# BACKPMAN21_Intfs.net
KiCad netlist of a schematic drawn in Altium Designer
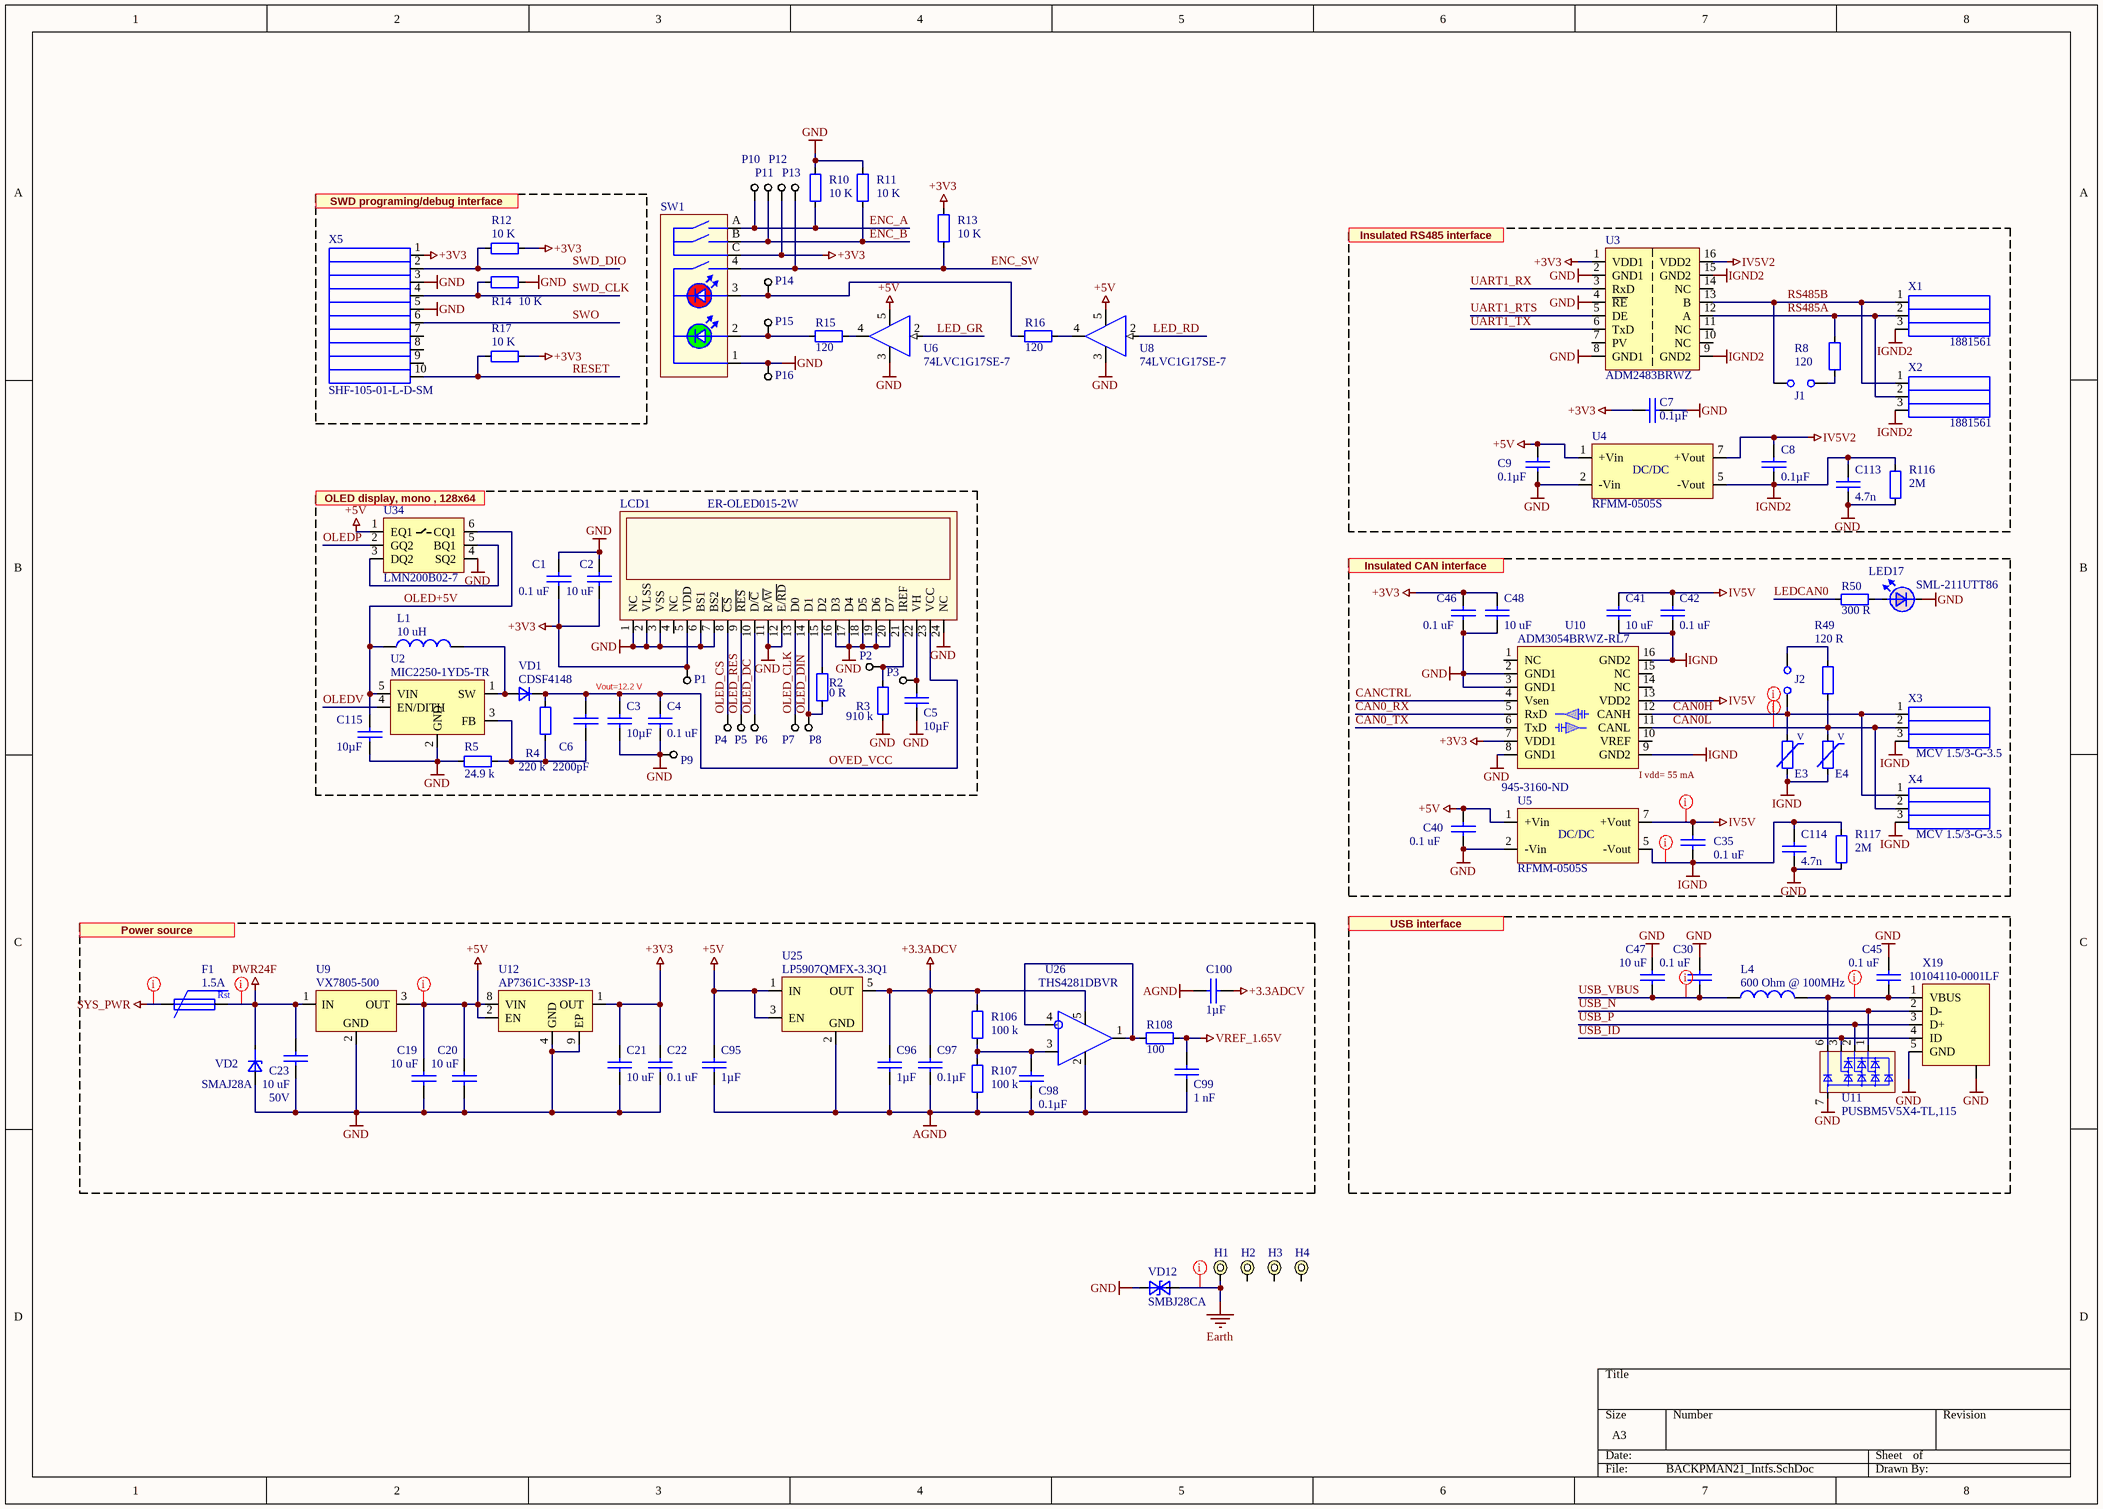
[diagram p0: BACKPMAN21_Intfs.SchDoc]

(export (version "E")
  (design (tool "Eeschema 10.0.6"))
  (components
    (comp (ref "C1")
      (value "0.1 uF")
      (footprint "1608[0603]")
      (description "0.1 uF, 50V, 10% , X7R,  0603 SMD MLC Capacitor")
      (fields (field (name "TOLERANCE") "±10%") (field (name "MANUFACTURER") "WALSIN"))
      (libsource (lib "ea_Capacitors") (part "CVNF100K0603-25"))
    )
    (comp (ref "C2")
      (value "10 uF")
      (footprint "0805-1206")
      (description "CAP CER 10UF 10V 10% X5R 0805")
      (fields (field (name "MANUFACTURER") "Taiyo Yuden") (field (name "TOLERANCE") "10%"))
      (libsource (lib "ea_Capacitors") (part "LMK212F106ZG-T"))
    )
    (comp (ref "C3")
      (value "10µF")
      (footprint "0805 CAP")
      (description "10µF, ±10%, 25V, X5R, 0805 (2012 Metric), -55°C ~ 85°C, -, General Purpose")
      (fields (field (name "PART NUMBER") "TMK212BBJ106KG-T") (field (name "MANUFACTURER") "Taiyo Yuden"))
      (libsource (lib "ea_PassivComps") (part "Capacitor"))
    )
    (comp (ref "C4")
      (value "0.1 uF")
      (footprint "1608[0603]")
      (description "0.1 uF, 50V, 10% , X7R,  0603 SMD MLC Capacitor")
      (fields (field (name "TOLERANCE") "±10%") (field (name "MANUFACTURER") "WALSIN"))
      (libsource (lib "ea_Capacitors") (part "CVNF100K0603-25"))
    )
    (comp (ref "C5")
      (value "10µF")
      (footprint "0805 CAP")
      (description "10µF, ±10%, 25V, X5R, 0805 (2012 Metric), -55°C ~ 85°C, -, General Purpose")
      (fields (field (name "PART NUMBER") "TMK212BBJ106KG-T") (field (name "MANUFACTURER") "Taiyo Yuden"))
      (libsource (lib "ea_PassivComps") (part "Capacitor"))
    )
    (comp (ref "C6")
      (value "2200pF")
      (footprint "0603 CAP")
      (description "2200pF, ±10%, 25V, X7R, 0603 (1608 Metric), -55°C ~ 125°C, -, General Purpose")
      (fields (field (name "PART NUMBER") "CC0603KRX7R8BB222") (field (name "MANUFACTURER") "Yageo"))
      (libsource (lib "ea_PassivComps") (part "Capacitor"))
    )
    (comp (ref "C7")
      (value "0.1µF")
      (footprint "0603 CAP")
      (description "0.1µF, ±10%, 16V, X7R, 0603 (1608 Metric), -55°C ~ 125°C, -, General Purpose")
      (fields
        (field (name "PART NUMBER") "CL10B104KO8NNNC")
        (field (name "MANUFACTURER") "Samsung Electro-Mechanics")
      )
      (libsource (lib "ea_PassivComps") (part "Capacitor"))
    )
    (comp (ref "C8")
      (value "0.1µF")
      (footprint "0603 CAP")
      (description "0.1µF, ±10%, 16V, X7R, 0603 (1608 Metric), -55°C ~ 125°C, -, General Purpose")
      (fields
        (field (name "PART NUMBER") "CL10B104KO8NNNC")
        (field (name "MANUFACTURER") "Samsung Electro-Mechanics")
      )
      (libsource (lib "ea_PassivComps") (part "Capacitor"))
    )
    (comp (ref "C9")
      (value "0.1µF")
      (footprint "0603 CAP")
      (description "0.1µF, ±10%, 16V, X7R, 0603 (1608 Metric), -55°C ~ 125°C, -, General Purpose")
      (fields
        (field (name "PART NUMBER") "CL10B104KO8NNNC")
        (field (name "MANUFACTURER") "Samsung Electro-Mechanics")
      )
      (libsource (lib "ea_PassivComps") (part "Capacitor"))
    )
    (comp (ref "C19")
      (value "10 uF")
      (footprint "0805-1206")
      (description "CAP CER 10UF 10V 10% X5R 0805")
      (fields (field (name "MANUFACTURER") "Taiyo Yuden") (field (name "TOLERANCE") "10%"))
      (libsource (lib "ea_Capacitors") (part "LMK212F106ZG-T"))
    )
    (comp (ref "C20")
      (value "10 uF")
      (footprint "0805-1206")
      (description "CAP CER 10UF 10V 10% X5R 0805")
      (fields (field (name "MANUFACTURER") "Taiyo Yuden") (field (name "TOLERANCE") "10%"))
      (libsource (lib "ea_Capacitors") (part "LMK212F106ZG-T"))
    )
    (comp (ref "C21")
      (value "10 uF")
      (footprint "0805-1206")
      (description "CAP CER 10UF 10V 10% X5R 0805")
      (fields (field (name "MANUFACTURER") "Taiyo Yuden") (field (name "TOLERANCE") "10%"))
      (libsource (lib "ea_Capacitors") (part "LMK212F106ZG-T"))
    )
    (comp (ref "C22")
      (value "0.1 uF")
      (footprint "1608[0603]")
      (description "0.1 uF, 50V, 10% , X7R,  0603 SMD MLC Capacitor")
      (fields (field (name "TOLERANCE") "±10%") (field (name "MANUFACTURER") "WALSIN"))
      (libsource (lib "ea_Capacitors") (part "CVNF100K0603-25"))
    )
    (comp (ref "C23")
      (value "10 uF")
      (footprint "3225[1210]")
      (description "10uF, 50V, 20%, Y5V (F), 1210")
      (fields
        (field (name "MANUFACTURER") "Taiyo Yuden")
        (field (name "TOLERANCE") "20%")
        (field (name "VOLTAGE") "50V")
      )
      (libsource (lib "ea_Capacitors") (part "GRM32DF51H106ZA01L"))
    )
    (comp (ref "C30")
      (value "0.1 uF")
      (footprint "1608[0603]")
      (description "0.1 uF, 50V, 10% , X7R,  0603 SMD MLC Capacitor")
      (fields (field (name "TOLERANCE") "±10%") (field (name "MANUFACTURER") "WALSIN"))
      (libsource (lib "ea_Capacitors") (part "CVNF100K0603-25"))
    )
    (comp (ref "C35")
      (value "0.1 uF")
      (footprint "1608[0603]")
      (description "0.1 uF, 50V, 10% , X7R,  0603 SMD MLC Capacitor")
      (fields (field (name "TOLERANCE") "±10%") (field (name "MANUFACTURER") "WALSIN"))
      (libsource (lib "ea_Capacitors") (part "CVNF100K0603-25"))
    )
    (comp (ref "C40")
      (value "0.1 uF")
      (footprint "1608[0603]")
      (description "0.1 uF, 50V, 10% , X7R,  0603 SMD MLC Capacitor")
      (fields (field (name "TOLERANCE") "±10%") (field (name "MANUFACTURER") "WALSIN"))
      (libsource (lib "ea_Capacitors") (part "CVNF100K0603-25"))
    )
    (comp (ref "C41")
      (value "10 uF")
      (footprint "0805-1206")
      (description "CAP CER 10UF 10V 10% X5R 0805")
      (fields (field (name "MANUFACTURER") "Taiyo Yuden") (field (name "TOLERANCE") "10%"))
      (libsource (lib "ea_Capacitors") (part "LMK212F106ZG-T"))
    )
    (comp (ref "C42")
      (value "0.1 uF")
      (footprint "1608[0603]")
      (description "0.1 uF, 50V, 10% , X7R,  0603 SMD MLC Capacitor")
      (fields (field (name "TOLERANCE") "±10%") (field (name "MANUFACTURER") "WALSIN"))
      (libsource (lib "ea_Capacitors") (part "CVNF100K0603-25"))
    )
    (comp (ref "C45")
      (value "0.1 uF")
      (footprint "1608[0603]")
      (description "0.1 uF, 50V, 10% , X7R,  0603 SMD MLC Capacitor")
      (fields (field (name "TOLERANCE") "±10%") (field (name "MANUFACTURER") "WALSIN"))
      (libsource (lib "ea_Capacitors") (part "CVNF100K0603-25"))
    )
    (comp (ref "C46")
      (value "0.1 uF")
      (footprint "1608[0603]")
      (description "0.1 uF, 50V, 10% , X7R,  0603 SMD MLC Capacitor")
      (fields (field (name "TOLERANCE") "±10%") (field (name "MANUFACTURER") "WALSIN"))
      (libsource (lib "ea_Capacitors") (part "CVNF100K0603-25"))
    )
    (comp (ref "C47")
      (value "10 uF")
      (footprint "0805-1206")
      (description "10 uF, 6.3V, X5R, 10%, 0805")
      (fields (field (name "MANUFACTURER") "Murata") (field (name "TOLERANCE") "10%"))
      (libsource (lib "ea_Capacitors") (part "GRM21BR60J106KE19L"))
    )
    (comp (ref "C48")
      (value "10 uF")
      (footprint "0805-1206")
      (description "CAP CER 10UF 10V 10% X5R 0805")
      (fields (field (name "MANUFACTURER") "Taiyo Yuden") (field (name "TOLERANCE") "10%"))
      (libsource (lib "ea_Capacitors") (part "LMK212F106ZG-T"))
    )
    (comp (ref "C95")
      (value "1µF")
      (footprint "0603 CAP")
      (description "1µF, ±10%, 16V, X5R, 0603 (1608 Metric), -55°C ~ 85°C, -, General Purpose")
      (fields (field (name "PART NUMBER") "EMK107BJ105KA-T") (field (name "MANUFACTURER") "Taiyo Yuden"))
      (libsource (lib "ea_PassivComps") (part "Capacitor"))
    )
    (comp (ref "C96")
      (value "1µF")
      (footprint "0603 CAP")
      (description "1µF, ±10%, 16V, X5R, 0603 (1608 Metric), -55°C ~ 85°C, -, General Purpose")
      (fields (field (name "PART NUMBER") "EMK107BJ105KA-T") (field (name "MANUFACTURER") "Taiyo Yuden"))
      (libsource (lib "ea_PassivComps") (part "Capacitor"))
    )
    (comp (ref "C97")
      (value "0.1µF")
      (footprint "0603 CAP")
      (description "0.1µF, ±10%, 50V, X8L, 0603 (1608 Metric), -55°C ~ 150°C, -, Automotive")
      (fields
        (field (name "PART NUMBER") "GCM188L81H104KA57D")
        (field (name "MANUFACTURER") "Murata Electronics North America")
      )
      (libsource (lib "ea_PassivComps") (part "Capacitor"))
    )
    (comp (ref "C98")
      (value "0.1µF")
      (footprint "0603 CAP")
      (description "0.1µF, ±10%, 50V, X8L, 0603 (1608 Metric), -55°C ~ 150°C, -, Automotive")
      (fields
        (field (name "PART NUMBER") "GCM188L81H104KA57D")
        (field (name "MANUFACTURER") "Murata Electronics North America")
      )
      (libsource (lib "ea_PassivComps") (part "Capacitor"))
    )
    (comp (ref "C99")
      (value "1 nF")
      (footprint "0603 CAP")
      (description "1000pF, ±5%, 50V, X7R, 0603 (1608 Metric), -55°C ~ 125°C, -, General Purpose")
      (fields (field (name "PART NUMBER") "CC0603JRX7R9BB102") (field (name "MANUFACTURER") "Yageo"))
      (libsource (lib "ea_PassivComps") (part "Capacitor"))
    )
    (comp (ref "C100")
      (value "1µF")
      (footprint "0603 CAP")
      (description "1µF, ±10%, 16V, X5R, 0603 (1608 Metric), -55°C ~ 85°C, -, General Purpose")
      (fields (field (name "PART NUMBER") "EMK107BJ105KA-T") (field (name "MANUFACTURER") "Taiyo Yuden"))
      (libsource (lib "ea_PassivComps") (part "Capacitor"))
    )
    (comp (ref "C113")
      (value "4.7n")
      (footprint "0805 CAP")
      (description "4700pF ±10% 1000V (1kV) Ceramic Capacitor X7R 0805 (2012 Metric),-55°C ~ 125°C")
      (fields (field (name "MANUFACTURER") "KEMET") (field (name "TOLERANCE") "10%"))
      (libsource (lib "ea_Capacitors") (part "C0805V472KDRACTU"))
    )
    (comp (ref "C114")
      (value "4.7n")
      (footprint "0805 CAP")
      (description "4700pF ±10% 1000V (1kV) Ceramic Capacitor X7R 0805 (2012 Metric),-55°C ~ 125°C")
      (fields (field (name "MANUFACTURER") "KEMET") (field (name "TOLERANCE") "10%"))
      (libsource (lib "ea_Capacitors") (part "C0805V472KDRACTU"))
    )
    (comp (ref "C115")
      (value "10µF")
      (footprint "0805 CAP")
      (description "10µF, ±10%, 25V, X5R, 0805 (2012 Metric), -55°C ~ 85°C, -, General Purpose")
      (fields (field (name "PART NUMBER") "TMK212BBJ106KG-T") (field (name "MANUFACTURER") "Taiyo Yuden"))
      (libsource (lib "ea_PassivComps") (part "Capacitor"))
    )
    (comp (ref "E3")
      (value "823 560 505 60")
      (footprint "0603")
      (description "SUPPRESSOR ESD 5VDC, 56pF,  0603, -40..+85C")
      (fields (field (name "MANUFACTURER") "Würth Elektronik") (field (name "VOLTAGE") "5V"))
      (libsource (lib "ea_TVS_protection") (part "823 560 501 01"))
    )
    (comp (ref "E4")
      (value "823 560 505 60")
      (footprint "0603")
      (description "SUPPRESSOR ESD 5VDC, 56pF,  0603, -40..+85C")
      (fields (field (name "MANUFACTURER") "Würth Elektronik") (field (name "VOLTAGE") "5V"))
      (libsource (lib "ea_TVS_protection") (part "823 560 501 01"))
    )
    (comp (ref "F1")
      (value "1.5A")
      (footprint "2920 (7351 Metric)")
      (description "PTC RESETTABLE 60V 750MA, It=1.5A, 0.3s 2920(7351)")
      (fields (field (name "MANUFACTURER") "Bel Fuse Inc.") (field (name "PARTNUM") "507-1743-1-ND"))
      (libsource (lib "ea_Fuses") (part "0ZCF0075AF2C"))
    )
    (comp (ref "H1")
      (value "Hole 5MM Plated")
      (footprint "HOLE_5MM plated")
      (libsource (lib "ea_Mechanical") (part "Hole 5MM Plated"))
    )
    (comp (ref "H2")
      (value "Hole 5MM Plated")
      (footprint "HOLE_5MM plated")
      (libsource (lib "ea_Mechanical") (part "Hole 5MM Plated"))
    )
    (comp (ref "H3")
      (value "Hole 5MM Plated")
      (footprint "HOLE_5MM plated")
      (libsource (lib "ea_Mechanical") (part "Hole 5MM Plated"))
    )
    (comp (ref "H4")
      (value "Hole 5MM Plated")
      (footprint "HOLE_5MM plated")
      (libsource (lib "ea_Mechanical") (part "Hole 5MM Plated"))
    )
    (comp (ref "J1")
      (value "PH1-02-TA-HT")
      (footprint "HDR1X2V")
      (description "2 Pos. 2.54 mm Single Row Through Hole Straight Pin Header")
      (fields (field (name "MANUFACTURER") "ADAM TECH"))
      (libsource (lib "ea_Commutation") (part "Jumper"))
    )
    (comp (ref "J2")
      (value "PH1-02-TA-HT")
      (footprint "HDR1X2V")
      (description "2 Pos. 2.54 mm Single Row Through Hole Straight Pin Header")
      (fields (field (name "MANUFACTURER") "ADAM TECH"))
      (libsource (lib "ea_Commutation") (part "Jumper"))
    )
    (comp (ref "L1")
      (value "10 uH")
      (footprint "VLS4012ET")
      (description "10uH, 890 mA, 0.228 Ohm, +-20%,- 40 C to + 105 C")
      (fields (field (name "MANUFACTURER") "TDK Corporation") (field (name "PARTNUM") "445-6681-1-ND"))
      (libsource (lib "ea_Inductors") (part "VLS4012ET-100M"))
    )
    (comp (ref "L4")
      (value "600 Ohm @ 100MHz")
      (footprint "0805")
      (description "FERRITE BEAD 600 OHM, 0805, -55°C ~ 125°C")
      (fields (field (name "MANUFACTURER") "TDK Corporation") (field (name "PARTNUM") "445-2206-1-ND"))
      (libsource (lib "ea_Inductors") (part "MPZ2012S601AT000"))
    )
    (comp (ref "LCD1")
      (value "ER-OLED015-2W")
      (footprint "ER-OLED015-2")
      (description "1.5\"OLED Display Serial 128x64 Module,SSD1309,White on Black")
      (fields
        (field (name "MANUFACTURER") "Orient Display")
        (field (name "PARTNUM") "2544-AOM12864A0-1.54WW-ND")
      )
      (libsource (lib "ea_LCD") (part "ER-OLED015-2W"))
    )
    (comp (ref "LED17")
      (value "SML-211UTT86")
      (footprint "0805 LED")
      (description "0805 red LED, hibright, 2 mA, 1.8V, 130°")
      (fields (field (name "MANUFACTURER") "Rohm") (field (name "PARTNUM") "511-1292-1-ND"))
      (libsource (lib "ea_Indicators") (part "SML-211UTT86"))
    )
    (comp (ref "P1")
      (value "Pin 0.9 mm")
      (footprint "Pin 0.9 mm")
      (libsource (lib "ea_Contacts") (part "Pin 0.9 mm"))
    )
    (comp (ref "P2")
      (value "Pin 0.9 mm")
      (footprint "Pin 0.9 mm")
      (libsource (lib "ea_Contacts") (part "Pin 0.9 mm"))
    )
    (comp (ref "P3")
      (value "Pin 0.9 mm")
      (footprint "Pin 0.9 mm")
      (libsource (lib "ea_Contacts") (part "Pin 0.9 mm"))
    )
    (comp (ref "P4")
      (value "Pin 0.9 mm")
      (footprint "Pin 0.9 mm")
      (libsource (lib "ea_Contacts") (part "Pin 0.9 mm"))
    )
    (comp (ref "P5")
      (value "Pin 0.9 mm")
      (footprint "Pin 0.9 mm")
      (libsource (lib "ea_Contacts") (part "Pin 0.9 mm"))
    )
    (comp (ref "P6")
      (value "Pin 0.9 mm")
      (footprint "Pin 0.9 mm")
      (libsource (lib "ea_Contacts") (part "Pin 0.9 mm"))
    )
    (comp (ref "P7")
      (value "Pin 0.9 mm")
      (footprint "Pin 0.9 mm")
      (libsource (lib "ea_Contacts") (part "Pin 0.9 mm"))
    )
    (comp (ref "P8")
      (value "Pin 0.9 mm")
      (footprint "Pin 0.9 mm")
      (libsource (lib "ea_Contacts") (part "Pin 0.9 mm"))
    )
    (comp (ref "P9")
      (value "Pin 0.9 mm")
      (footprint "Pin 0.9 mm")
      (libsource (lib "ea_Contacts") (part "Pin 0.9 mm"))
    )
    (comp (ref "P10")
      (value "Pin 0.9 mm")
      (footprint "Pin 0.9 mm")
      (libsource (lib "ea_Contacts") (part "Pin 0.9 mm"))
    )
    (comp (ref "P11")
      (value "Pin 0.9 mm")
      (footprint "Pin 0.9 mm")
      (libsource (lib "ea_Contacts") (part "Pin 0.9 mm"))
    )
    (comp (ref "P12")
      (value "Pin 0.9 mm")
      (footprint "Pin 0.9 mm")
      (libsource (lib "ea_Contacts") (part "Pin 0.9 mm"))
    )
    (comp (ref "P13")
      (value "Pin 0.9 mm")
      (footprint "Pin 0.9 mm")
      (libsource (lib "ea_Contacts") (part "Pin 0.9 mm"))
    )
    (comp (ref "P14")
      (value "Pin 0.9 mm")
      (footprint "Pin 0.9 mm")
      (libsource (lib "ea_Contacts") (part "Pin 0.9 mm"))
    )
    (comp (ref "P15")
      (value "Pin 0.9 mm")
      (footprint "Pin 0.9 mm")
      (libsource (lib "ea_Contacts") (part "Pin 0.9 mm"))
    )
    (comp (ref "P16")
      (value "Pin 0.9 mm")
      (footprint "Pin 0.9 mm")
      (libsource (lib "ea_Contacts") (part "Pin 0.9 mm"))
    )
    (comp (ref "R2")
      (value "0 R")
      (footprint "0603")
      (description "0 R, Jumper, 0603, SMD Resistor, -55°C ~ 155°C")
      (fields (field (name "MANUFACTURER") "Yageo") (field (name "VOLTAGE") "75 V"))
      (libsource (lib "ea_Resistors_0603") (part "RC0603FR-070RL"))
    )
    (comp (ref "R3")
      (value "910 k")
      (footprint "0603")
      (fields
        (field (name "MANUFACTURER") "Stackpole Electronics Inc.")
        (field (name "TOLERANCE") "±1%")
        (field (name "VOLTAGE") "75V")
      )
      (libsource (lib "") (part "Resistor_1"))
    )
    (comp (ref "R4")
      (value "220 k")
      (footprint "0603")
      (fields
        (field (name "MANUFACTURER") "Stackpole Electronics Inc.")
        (field (name "TOLERANCE") "±1%")
        (field (name "VOLTAGE") "75V")
      )
      (libsource (lib "") (part "Resistor_1"))
    )
    (comp (ref "R5")
      (value "24.9 k")
      (footprint "0603")
      (fields
        (field (name "MANUFACTURER") "Stackpole Electronics Inc.")
        (field (name "TOLERANCE") "±1%")
        (field (name "VOLTAGE") "75V")
      )
      (libsource (lib "ea_PassivComps") (part "Resistor"))
    )
    (comp (ref "R8")
      (value "120")
      (footprint "0603")
      (fields
        (field (name "MANUFACTURER") "Stackpole Electronics Inc.")
        (field (name "TOLERANCE") "±1%")
        (field (name "VOLTAGE") "75V")
      )
      (libsource (lib "") (part "Resistor_1"))
    )
    (comp (ref "R10")
      (value "10 K")
      (footprint "0603")
      (description "10 K, 1%, 0603, SMD Resistor, Taped")
      (fields (field (name "MANUFACTURER") "Vishay") (field (name "TOLERANCE") "1%"))
      (libsource (lib "") (part "RL0603K010-1_1"))
    )
    (comp (ref "R11")
      (value "10 K")
      (footprint "0603")
      (description "10 K, 1%, 0603, SMD Resistor, Taped")
      (fields (field (name "MANUFACTURER") "Vishay") (field (name "TOLERANCE") "1%"))
      (libsource (lib "") (part "RL0603K010-1_1"))
    )
    (comp (ref "R12")
      (value "10 K")
      (footprint "0603")
      (description "10 K, 1%, 0603, SMD Resistor, Taped")
      (fields (field (name "MANUFACTURER") "Vishay") (field (name "TOLERANCE") "1%"))
      (libsource (lib "ea_Resistors_0603") (part "RL0603K010-1"))
    )
    (comp (ref "R13")
      (value "10 K")
      (footprint "0603")
      (description "10 K, 1%, 0603, SMD Resistor, Taped")
      (fields (field (name "MANUFACTURER") "Vishay") (field (name "TOLERANCE") "1%"))
      (libsource (lib "") (part "RL0603K010-1_1"))
    )
    (comp (ref "R14")
      (value "10 K")
      (footprint "0603")
      (description "10 K, 1%, 0603, SMD Resistor, Taped")
      (fields (field (name "MANUFACTURER") "Vishay") (field (name "TOLERANCE") "1%"))
      (libsource (lib "ea_Resistors_0603") (part "RL0603K010-1"))
    )
    (comp (ref "R15")
      (value "120")
      (footprint "0603")
      (fields
        (field (name "MANUFACTURER") "Stackpole Electronics Inc.")
        (field (name "TOLERANCE") "±1%")
        (field (name "VOLTAGE") "75V")
      )
      (libsource (lib "ea_PassivComps") (part "Resistor"))
    )
    (comp (ref "R16")
      (value "120")
      (footprint "0603")
      (fields
        (field (name "MANUFACTURER") "Stackpole Electronics Inc.")
        (field (name "TOLERANCE") "±1%")
        (field (name "VOLTAGE") "75V")
      )
      (libsource (lib "ea_PassivComps") (part "Resistor"))
    )
    (comp (ref "R17")
      (value "10 K")
      (footprint "0603")
      (description "10 K, 1%, 0603, SMD Resistor, Taped")
      (fields (field (name "MANUFACTURER") "Vishay") (field (name "TOLERANCE") "1%"))
      (libsource (lib "ea_Resistors_0603") (part "RL0603K010-1"))
    )
    (comp (ref "R49")
      (value "120 R")
      (footprint "0603")
      (description "120 R, 1%, 0603, SMD Resistor, Taped")
      (fields (field (name "MANUFACTURER") "Vishay") (field (name "TOLERANCE") "±1%"))
      (libsource (lib "ea_Resistors") (part "RL0603E120-1"))
    )
    (comp (ref "R50")
      (value "300 R")
      (footprint "0603")
      (description "300 R, 1%, 0.1 W, 0603, SMD Resistor, Taped")
      (fields (field (name "MANUFACTURER") "Vishay/Dale") (field (name "TOLERANCE") "1%"))
      (libsource (lib "ea_Resistors_0603") (part "CRCW0603300RFKEA"))
    )
    (comp (ref "R106")
      (value "100 k")
      (footprint "0603")
      (description "100 kOhms, ±0.1%, 0.1W, 1/10W, Thin Film, ±25ppm/°C, 0603 (1608 Metric), -55°C ~ 155°C, -")
      (fields (field (name "MANUFACTURER") "Yageo") (field (name "TOLERANCE") "±0.1%"))
      (libsource (lib "") (part "Resistor_1"))
    )
    (comp (ref "R107")
      (value "100 k")
      (footprint "0603")
      (description "100 kOhms, ±0.1%, 0.1W, 1/10W, Thin Film, ±25ppm/°C, 0603 (1608 Metric), -55°C ~ 155°C, -")
      (fields (field (name "MANUFACTURER") "Yageo") (field (name "TOLERANCE") "±0.1%"))
      (libsource (lib "") (part "Resistor_1"))
    )
    (comp (ref "R108")
      (value "100")
      (footprint "0603")
      (fields
        (field (name "MANUFACTURER") "Stackpole Electronics Inc.")
        (field (name "TOLERANCE") "±1%")
        (field (name "VOLTAGE") "75V")
      )
      (libsource (lib "ea_PassivComps") (part "Resistor"))
    )
    (comp (ref "R116")
      (value "2M")
      (footprint "1206")
      (description "2 MOhms ±1% 0.25W, 1/4W Chip Resistor 1206 (3216 Metric) High Voltage Thick Film,-55°C ~ 155°C")
      (fields (field (name "MANUFACTURER") "Vishay Dale") (field (name "TOLERANCE") "±1%"))
      (libsource (lib "ea_Resistors") (part "RCV12062M00FKEA"))
    )
    (comp (ref "R117")
      (value "2M")
      (footprint "1206")
      (description "2 MOhms ±1% 0.25W, 1/4W Chip Resistor 1206 (3216 Metric) High Voltage Thick Film,-55°C ~ 155°C")
      (fields (field (name "MANUFACTURER") "Vishay Dale") (field (name "TOLERANCE") "±1%"))
      (libsource (lib "ea_Resistors") (part "RCV12062M00FKEA"))
    )
    (comp (ref "SW1")
      (value "PEL12D-4225S-S2024")
      (footprint "PEL12D-4225S-S2024")
      (description "Rotary Encoder Mechanical 24 Quadrature (Incremental) Vertical")
      (fields (field (name "MANUFACTURER") "Bourns Inc.") (field (name "PARTNUM") "PEL12D-4225S-S2024-ND"))
      (libsource (lib "ea_Commutation") (part "PEL12D-4225S-S2024"))
    )
    (comp (ref "U2")
      (value "MIC2250-1YD5-TR")
      (footprint "SOT23-5")
      (description "Boost DC/DC, 2.5..5.5 to 1.24..32V, 900vA, 2.5Mhz, SOT-23-5, -40..+125 C")
      (fields (field (name "PARTNUM") "576-3967-1-ND") (field (name "MANUFACTURER") "Microchip Technology"))
      (libsource (lib "ea_IC_Power_Reg_Ref_Sw") (part "MIC2250-1YD5-TR"))
    )
    (comp (ref "U3")
      (value "ADM2483BRWZ")
      (footprint "SO-G16/D10.4")
      (description "RS422, RS485 Digital Isolator 2500Vrms 3 Channel 500kbps 25kV/µs CMTI 16-SOIC, -40°C ~ 85°C")
      (fields (field (name "MANUFACTURER") "Analog Divices") (field (name "PARTNUM") "ADM2483BRWZ-ND"))
      (libsource (lib "ea_IC_Interfaces") (part "ADM2483BRWZ"))
    )
    (comp (ref "U4")
      (value "RFMM-0505S")
      (footprint "Recom 7-SIP module")
      (description "1W DC-DC Unregulated Single Output , 5V in, 5 V out,  200mA, 4 kV, -40°C ~ 85°C")
      (fields (field (name "MANUFACTURER") "Recom Power") (field (name "PARTNUM") "945-3160-ND"))
      (libsource (lib "ea_PowerSources") (part "RFMM-0505S"))
    )
    (comp (ref "U5")
      (value "RFMM-0505S")
      (footprint "Recom 7-SIP module")
      (description "1W DC-DC Unregulated Single Output , 5V in, 5 V out,  200mA, 4 kV, -40°C ~ 85°C")
      (fields
        (field (name "MANUFACTURER") "Recom Power")
        (field (name "PARTNUM") "945-3160-ND")
        (field (name "SUPPLIER PART NUMBER 1") "945-3160-ND")
      )
      (libsource (lib "ea_PowerSources") (part "RFMM-0505S"))
    )
    (comp (ref "U6")
      (value "74LVC1G17SE-7")
      (footprint "SOT-353 ON Semi")
      (description "IC SGL SCHMITT BUFFER SOT353")
      (fields
        (field (name "MANUFACTURER") "Diodes Incorporated")
        (field (name "PARTNUM") "74LVC1G17SE-7CT-ND")
      )
      (libsource (lib "ea_IC_Logic") (part "74LVC1G17SE-7"))
    )
    (comp (ref "U8")
      (value "74LVC1G17SE-7")
      (footprint "SOT-353 ON Semi")
      (description "IC SGL SCHMITT BUFFER SOT353")
      (fields
        (field (name "MANUFACTURER") "Diodes Incorporated")
        (field (name "PARTNUM") "74LVC1G17SE-7CT-ND")
      )
      (libsource (lib "ea_IC_Logic") (part "74LVC1G17SE-7"))
    )
    (comp (ref "U9")
      (value "VX7805-500")
      (footprint "VX7805-500")
      (description "Linear Regulator Replacement DC DC Converter 1 Output 5V 500mA 6.5V - 36V Input")
      (fields (field (name "MANUFACTURER") "CUI Inc.") (field (name "PARTNUM") "102-4244-ND"))
      (libsource (lib "ea_IC_Power_Reg_Ref_Sw") (part "VX7805-500"))
    )
    (comp (ref "U10")
      (value "ADM3054BRWZ-RL7")
      (footprint "SO-G16/D10.4")
      (description "IC Isol TXRX CAN HS 16SOIC")
      (fields (field (name "MANUFACTURER") "Analog Divices") (field (name "PARTNUM") "ADM3054BRWZ-RL7CT-ND"))
      (libsource (lib "ea_IC_Interfaces") (part "ADM3054BRWZ-RL7"))
    )
    (comp (ref "U11")
      (value "PUSBM5V5X4-TL,115")
      (footprint "DFN1616-6")
      (description "TVS DIODE 5.5VWM 12VC 6HXSON")
      (fields (field (name "MANUFACTURER") "NXP Semiconductors") (field (name "PARTNUM") "568-10921-1-ND"))
      (libsource (lib "ea_TVS_protection") (part "PUSBM5V5X4-TL,115"))
    )
    (comp (ref "U12")
      (value "AP7361C-33SP-13")
      (footprint "SOIC-8 EDP")
      (description "LDO, 3.3 V, 1A, 0.36V@1A, Vin=6V max, -40..+85C, 8-SO-EP")
      (fields
        (field (name "PARTNUM") "AP7361C-33SP-13DICT-ND")
        (field (name "MANUFACTURER") "Diodes Incorporated")
      )
      (libsource (lib "ea_IC_Power_Reg_Ref_Sw") (part "AP7361C-33SP-13"))
    )
    (comp (ref "U25")
      (value "LP5907QMFX-3.3Q1")
      (footprint "SOT23-5")
      (description "LDO 3.3 V, 250 mA, Vin < 5.5V, Iq < 12uA, -40..+125 C, SOT23-5")
      (fields (field (name "MANUFACTURER") "Texas Instruments") (field (name "PARTNUM") "296-40365-1-ND"))
      (libsource (lib "ea_IC_Power_Reg_Ref_Sw") (part "LP5907QMFX-3.3Q1"))
    )
    (comp (ref "U26")
      (value "THS4281DBVR")
      (footprint "SOT23-5")
      (description "Voltage Feedback Amplifier 1 Circuit Rail-to-Rail SOT-23-5")
      (fields (field (name "MANUFACTURER") "Texas Instruments") (field (name "PARTNUM") "296-39224-1-ND"))
      (libsource (lib "ea_IC_OPAmps_AnComparators") (part "THS4281DBVR"))
    )
    (comp (ref "U34")
      (value "LMN200B02-7")
      (footprint "SOT363")
      (fields (field (name "MANUFACTURER") "Diodes Incorporated") (field (name "PARTNUM") "LMN200B02DICT-ND"))
      (libsource (lib "ea_IC_drivers") (part "LMN200B02-7"))
    )
    (comp (ref "VD1")
      (value "CDSF4148")
      (footprint "1005")
      (description "150 mA, 75V, 1005, 125 C")
      (fields (field (name "MANUFACTURER") "Comchip Technology") (field (name "PARTNUM") "641-1004-1-ND"))
      (libsource (lib "ea_Diodes") (part "CDSF4148"))
    )
    (comp (ref "VD2")
      (value "SMAJ28A")
      (footprint "SMA")
      (description "DIODE TVS 28V 400W UNI 5% SMD")
      (fields (field (name "MANUFACTURER") "Bourns Inc.") (field (name "PARTNUM") "SMAJ28ABCT-ND"))
      (libsource (lib "ea_TVS_protection") (part "SMAJ28A"))
    )
    (comp (ref "VD12")
      (value "SMBJ28CA")
      (footprint "DO-214AA_SMBJ BI")
      (description "TVS 600W 28V Bidirectional")
      (fields (field (name "MANUFACTURER") "Littelfuse") (field (name "PARTNUM") "SMBJ28CABCT-ND"))
      (libsource (lib "ea_TVS_protection") (part "SMBJ28CA"))
    )
    (comp (ref "X1")
      (value "1881561")
      (footprint "1881561")
      (description "Printed-circuit board connector - MCV 0,5/ 3-G-2,5 - 1881561")
      (fields (field (name "MANUFACTURER") "Phoenix Contact"))
      (libsource (lib "ea_Connectors_2.5_mm_pitch") (part "1881561"))
    )
    (comp (ref "X2")
      (value "1881561")
      (footprint "1881561")
      (description "Printed-circuit board connector - MCV 0,5/ 3-G-2,5 - 1881561")
      (fields (field (name "MANUFACTURER") "Phoenix Contact"))
      (libsource (lib "ea_Connectors_2.5_mm_pitch") (part "1881561"))
    )
    (comp (ref "X3")
      (value "MCV 1.5/3-G-3.5")
      (footprint "mcv1.5-3-g_3.5 green + MC 1,5 3-ST-3,5 - 1840379")
      (description "HEADER, VERTICAL, 3.5MM, 3WAY")
      (fields (field (name "MANUFACTURER") "PHOENIX CONTACT") (field (name "PARTNUM") "1843619"))
      (libsource (lib "ea_PhoenixContacts") (part "MCV 1.5/3-G-3.5"))
    )
    (comp (ref "X4")
      (value "MCV 1.5/3-G-3.5")
      (footprint "mcv1.5-3-g_3.5 green + MC 1,5 3-ST-3,5 - 1840379")
      (description "HEADER, VERTICAL, 3.5MM, 3WAY")
      (fields (field (name "MANUFACTURER") "PHOENIX CONTACT") (field (name "PARTNUM") "1843619"))
      (libsource (lib "ea_PhoenixContacts") (part "MCV 1.5/3-G-3.5"))
    )
    (comp (ref "X5")
      (value "SHF-105-01-L-D-SM")
      (footprint "SHF-105-01-L-D-SM")
      (description "10 Positions Header Connector 0.050\" (1.27mm) Surface Mount Gold")
      (fields (field (name "MANUFACTURER") "Samtec Inc."))
      (libsource (lib "ea_Connectors_1.27_mm_pitch") (part "SHF-105-01-L-D-SM"))
    )
    (comp (ref "X19")
      (value "10104110-0001LF")
      (footprint "FCI micro USB B receptacle SMD")
      (description "USB - micro B USB 2.0 Receptacle Connector 5 Position Surface Mount, Right Angle")
      (fields (field (name "MANUFACTURER") "Amphenol FCI") (field (name "PARTNUM") "609-4052-1-ND"))
      (libsource (lib "ea_Connectors_USB") (part "10104110-0001LF"))
    )
  )
  (nets
    (net (code "1") (name "+3.3ADCV") (class "Default")
      (node (ref "C100") (pin "1") (pinfunction "1_1") (pintype "passive"))
      (node (ref "C96") (pin "2") (pinfunction "2_2") (pintype "passive"))
      (node (ref "C97") (pin "1") (pinfunction "1_1") (pintype "passive"))
      (node (ref "R106") (pin "2") (pinfunction "2_2") (pintype "passive"))
      (node (ref "U25") (pin "5") (pinfunction "OUT_5") (pintype "power_in"))
      (node (ref "U26") (pin "5") (pinfunction "V+_5") (pintype "power_in"))
    )
    (net (code "2") (name "+3V3") (class "Default")
      (node (ref "C1") (pin "2") (pinfunction "2_2") (pintype "passive"))
      (node (ref "C2") (pin "1") (pinfunction "1_1") (pintype "passive"))
      (node (ref "C21") (pin "2") (pinfunction "2_2") (pintype "passive"))
      (node (ref "C22") (pin "2") (pinfunction "2_2") (pintype "passive"))
      (node (ref "C46") (pin "2") (pinfunction "2_2") (pintype "passive"))
      (node (ref "C48") (pin "2") (pinfunction "2_2") (pintype "passive"))
      (node (ref "C7") (pin "1") (pinfunction "1_1") (pintype "passive"))
      (node (ref "LCD1") (pin "5") (pinfunction "VDD_5") (pintype "passive"))
      (node (ref "P1") (pin "1") (pinfunction "1_1") (pintype "passive"))
      (node (ref "P12") (pin "1") (pinfunction "1_1") (pintype "passive"))
      (node (ref "R12") (pin "2") (pinfunction "2_2") (pintype "passive"))
      (node (ref "R13") (pin "2") (pinfunction "2_2") (pintype "passive"))
      (node (ref "R17") (pin "2") (pinfunction "2_2") (pintype "passive"))
      (node (ref "SW1") (pin "C") (pinfunction "C_C") (pintype "passive"))
      (node (ref "U10") (pin "7") (pinfunction "VDD1_7") (pintype "passive"))
      (node (ref "U12") (pin "1") (pinfunction "OUT_1") (pintype "passive"))
      (node (ref "U3") (pin "1") (pinfunction "VDD1_1") (pintype "passive"))
      (node (ref "X5") (pin "1") (pinfunction "1_1") (pintype "passive"))
    )
    (net (code "3") (name "+5V") (class "Default")
      (node (ref "C19") (pin "2") (pinfunction "2_2") (pintype "passive"))
      (node (ref "C20") (pin "2") (pinfunction "2_2") (pintype "passive"))
      (node (ref "C40") (pin "2") (pinfunction "2_2") (pintype "passive"))
      (node (ref "C9") (pin "2") (pinfunction "2_2") (pintype "passive"))
      (node (ref "C95") (pin "2") (pinfunction "2_2") (pintype "passive"))
      (node (ref "U12") (pin "2") (pinfunction "EN_2") (pintype "passive"))
      (node (ref "U12") (pin "8") (pinfunction "VIN_8") (pintype "passive"))
      (node (ref "U25") (pin "1") (pinfunction "IN_1") (pintype "power_in"))
      (node (ref "U25") (pin "3") (pinfunction "EN_3") (pintype "power_in"))
      (node (ref "U34") (pin "1") (pinfunction "EQ1_1") (pintype "passive"))
      (node (ref "U4") (pin "1") (pinfunction "+Vin_1") (pintype "passive"))
      (node (ref "U5") (pin "1") (pinfunction "+Vin_1") (pintype "passive"))
      (node (ref "U6") (pin "5") (pinfunction "VCC_5") (pintype "power_in"))
      (node (ref "U8") (pin "5") (pinfunction "VCC_5") (pintype "power_in"))
      (node (ref "U9") (pin "3") (pinfunction "OUT_3") (pintype "power_in"))
    )
    (net (code "4") (name "/CAN0H") (class "Default")
      (node (ref "E3") (pin "2") (pinfunction "2_2") (pintype "passive"))
      (node (ref "J2") (pin "2") (pinfunction "2_2") (pintype "passive"))
      (node (ref "U10") (pin "12") (pinfunction "CANH_12") (pintype "passive"))
      (node (ref "X3") (pin "1") (pinfunction "1_1") (pintype "passive"))
      (node (ref "X4") (pin "1") (pinfunction "1_1") (pintype "passive"))
    )
    (net (code "5") (name "/CAN0L") (class "Default")
      (node (ref "E4") (pin "2") (pinfunction "2_2") (pintype "passive"))
      (node (ref "R49") (pin "1") (pinfunction "1_1") (pintype "passive"))
      (node (ref "U10") (pin "11") (pinfunction "CANL_11") (pintype "passive"))
      (node (ref "X3") (pin "2") (pinfunction "2_2") (pintype "passive"))
      (node (ref "X4") (pin "2") (pinfunction "2_2") (pintype "passive"))
    )
    (net (code "6") (name "/CAN0_RX") (class "Default")
      (node (ref "U10") (pin "5") (pinfunction "RxD_5") (pintype "passive"))
    )
    (net (code "7") (name "/CAN0_TX") (class "Default")
      (node (ref "U10") (pin "6") (pinfunction "TxD_6") (pintype "passive"))
    )
    (net (code "8") (name "/CANCTRL") (class "Default")
      (node (ref "U10") (pin "4") (pinfunction "Vsen_4") (pintype "passive"))
    )
    (net (code "9") (name "/ENC_A") (class "Default")
      (node (ref "P10") (pin "1") (pinfunction "1_1") (pintype "passive"))
      (node (ref "R10") (pin "1") (pinfunction "1_1") (pintype "passive"))
      (node (ref "SW1") (pin "A") (pinfunction "A_A") (pintype "passive"))
    )
    (net (code "10") (name "/ENC_B") (class "Default")
      (node (ref "P11") (pin "1") (pinfunction "1_1") (pintype "passive"))
      (node (ref "R11") (pin "1") (pinfunction "1_1") (pintype "passive"))
      (node (ref "SW1") (pin "B") (pinfunction "B_B") (pintype "passive"))
    )
    (net (code "11") (name "/ENC_SW") (class "Default")
      (node (ref "P13") (pin "1") (pinfunction "1_1") (pintype "passive"))
      (node (ref "R13") (pin "1") (pinfunction "1_1") (pintype "passive"))
      (node (ref "SW1") (pin "4") (pinfunction "4_4") (pintype "passive"))
    )
    (net (code "12") (name "/LEDCAN0") (class "Default")
      (node (ref "R50") (pin "2") (pinfunction "2_2") (pintype "passive"))
    )
    (net (code "13") (name "/LED_GR") (class "Default")
      (node (ref "U6") (pin "2") (pinfunction "A_2") (pintype "input"))
    )
    (net (code "14") (name "/LED_RD") (class "Default")
      (node (ref "U8") (pin "2") (pinfunction "A_2") (pintype "input"))
    )
    (net (code "15") (name "/OLED+5V") (class "Default")
      (node (ref "C115") (pin "1") (pinfunction "1_1") (pintype "passive"))
      (node (ref "L1") (pin "1") (pinfunction "1_1") (pintype "passive"))
      (node (ref "U2") (pin "5") (pinfunction "VIN_5") (pintype "passive"))
      (node (ref "U34") (pin "6") (pinfunction "CQ1_6") (pintype "passive"))
    )
    (net (code "16") (name "/OLEDP") (class "Default")
      (node (ref "U34") (pin "2") (pinfunction "GQ2_2") (pintype "passive"))
    )
    (net (code "17") (name "/OLEDV") (class "Default")
      (node (ref "U2") (pin "4") (pinfunction "EN/DITH_4") (pintype "passive"))
    )
    (net (code "18") (name "/OLED_CLK") (class "Default")
      (node (ref "LCD1") (pin "13") (pinfunction "D0_13") (pintype "passive"))
      (node (ref "P7") (pin "1") (pinfunction "1_1") (pintype "passive"))
    )
    (net (code "19") (name "/OLED_CS") (class "Default")
      (node (ref "LCD1") (pin "8") (pinfunction "~{CS}_8") (pintype "passive"))
      (node (ref "P4") (pin "1") (pinfunction "1_1") (pintype "passive"))
    )
    (net (code "20") (name "/OLED_DC") (class "Default")
      (node (ref "LCD1") (pin "10") (pinfunction "D/~{C}_10") (pintype "passive"))
      (node (ref "P6") (pin "1") (pinfunction "1_1") (pintype "passive"))
    )
    (net (code "21") (name "/OLED_DIN") (class "Default")
      (node (ref "LCD1") (pin "14") (pinfunction "D1_14") (pintype "passive"))
      (node (ref "P8") (pin "1") (pinfunction "1_1") (pintype "passive"))
      (node (ref "R2") (pin "1") (pinfunction "1_1") (pintype "passive"))
    )
    (net (code "22") (name "/OLED_RES") (class "Default")
      (node (ref "LCD1") (pin "9") (pinfunction "~{RES}_9") (pintype "passive"))
      (node (ref "P5") (pin "1") (pinfunction "1_1") (pintype "passive"))
    )
    (net (code "23") (name "/OVED_VCC") (class "Default")
      (node (ref "C3") (pin "1") (pinfunction "1_1") (pintype "passive"))
      (node (ref "C4") (pin "2") (pinfunction "2_2") (pintype "passive"))
      (node (ref "C6") (pin "1") (pinfunction "1_1") (pintype "passive"))
      (node (ref "LCD1") (pin "23") (pinfunction "VCC_23") (pintype "passive"))
      (node (ref "R4") (pin "2") (pinfunction "2_2") (pintype "passive"))
      (node (ref "VD1") (pin "1") (pinfunction "1_1") (pintype "passive"))
    )
    (net (code "24") (name "/RESET") (class "Default")
      (node (ref "R17") (pin "1") (pinfunction "1_1") (pintype "passive"))
      (node (ref "X5") (pin "10") (pinfunction "10_10") (pintype "passive"))
    )
    (net (code "25") (name "/RS485A") (class "Default")
      (node (ref "R8") (pin "2") (pinfunction "2_2") (pintype "passive"))
      (node (ref "U3") (pin "12") (pinfunction "A_12") (pintype "passive"))
      (node (ref "X1") (pin "2") (pinfunction "2_2") (pintype "passive"))
      (node (ref "X2") (pin "2") (pinfunction "2_2") (pintype "passive"))
    )
    (net (code "26") (name "/RS485B") (class "Default")
      (node (ref "J1") (pin "1") (pinfunction "1_1") (pintype "passive"))
      (node (ref "U3") (pin "13") (pinfunction "B_13") (pintype "passive"))
      (node (ref "X1") (pin "1") (pinfunction "1_1") (pintype "passive"))
      (node (ref "X2") (pin "1") (pinfunction "1_1") (pintype "passive"))
    )
    (net (code "27") (name "/SWD_CLK") (class "Default")
      (node (ref "R14") (pin "1") (pinfunction "1_1") (pintype "passive"))
      (node (ref "X5") (pin "4") (pinfunction "4_4") (pintype "passive"))
    )
    (net (code "28") (name "/SWD_DIO") (class "Default")
      (node (ref "R12") (pin "1") (pinfunction "1_1") (pintype "passive"))
      (node (ref "X5") (pin "2") (pinfunction "2_2") (pintype "passive"))
    )
    (net (code "29") (name "/SWO") (class "Default")
      (node (ref "X5") (pin "6") (pinfunction "6_6") (pintype "passive"))
    )
    (net (code "30") (name "/UART1_RTS") (class "Default")
      (node (ref "U3") (pin "5") (pinfunction "DE_5") (pintype "passive"))
    )
    (net (code "31") (name "/UART1_RX") (class "Default")
      (node (ref "U3") (pin "3") (pinfunction "RxD_3") (pintype "passive"))
    )
    (net (code "32") (name "/UART1_TX") (class "Default")
      (node (ref "U3") (pin "6") (pinfunction "TxD_6") (pintype "passive"))
    )
    (net (code "33") (name "/USB_ID") (class "Default")
      (node (ref "U11") (pin "3") (pinfunction "3_3") (pintype "passive"))
      (node (ref "X19") (pin "4") (pinfunction "ID_4") (pintype "passive"))
    )
    (net (code "34") (name "/USB_N") (class "Default")
      (node (ref "U11") (pin "1") (pinfunction "1_1") (pintype "passive"))
      (node (ref "X19") (pin "2") (pinfunction "D-_2") (pintype "bidirectional"))
    )
    (net (code "35") (name "/USB_P") (class "Default")
      (node (ref "U11") (pin "2") (pinfunction "2_2") (pintype "passive"))
      (node (ref "X19") (pin "3") (pinfunction "D+_3") (pintype "bidirectional"))
    )
    (net (code "36") (name "/USB_VBUS") (class "Default")
      (node (ref "C30") (pin "1") (pinfunction "1_1") (pintype "passive"))
      (node (ref "C47") (pin "1") (pinfunction "1_1") (pintype "passive"))
      (node (ref "L4") (pin "2") (pinfunction "2_2") (pintype "passive"))
    )
    (net (code "37") (name "AGND") (class "Default")
      (node (ref "C100") (pin "2") (pinfunction "2_2") (pintype "passive"))
      (node (ref "C95") (pin "1") (pinfunction "1_1") (pintype "passive"))
      (node (ref "C96") (pin "1") (pinfunction "1_1") (pintype "passive"))
      (node (ref "C97") (pin "2") (pinfunction "2_2") (pintype "passive"))
      (node (ref "C98") (pin "2") (pinfunction "2_2") (pintype "passive"))
      (node (ref "C99") (pin "2") (pinfunction "2_2") (pintype "passive"))
      (node (ref "R107") (pin "1") (pinfunction "1_1") (pintype "passive"))
      (node (ref "U25") (pin "2") (pinfunction "GND_2") (pintype "power_in"))
      (node (ref "U26") (pin "2") (pinfunction "GND_2") (pintype "power_in"))
    )
    (net (code "38") (name "Earth") (class "Default")
      (node (ref "H1") (pin "0") (pinfunction "0_0") (pintype "passive"))
      (node (ref "VD12") (pin "2") (pinfunction "A_2") (pintype "passive"))
    )
    (net (code "39") (name "GND") (class "Default")
      (node (ref "C1") (pin "1") (pinfunction "1_1") (pintype "passive"))
      (node (ref "C113") (pin "2") (pinfunction "2_2") (pintype "passive"))
      (node (ref "C114") (pin "2") (pinfunction "2_2") (pintype "passive"))
      (node (ref "C115") (pin "2") (pinfunction "2_2") (pintype "passive"))
      (node (ref "C19") (pin "1") (pinfunction "1_1") (pintype "passive"))
      (node (ref "C2") (pin "2") (pinfunction "2_2") (pintype "passive"))
      (node (ref "C20") (pin "1") (pinfunction "1_1") (pintype "passive"))
      (node (ref "C21") (pin "1") (pinfunction "1_1") (pintype "passive"))
      (node (ref "C22") (pin "1") (pinfunction "1_1") (pintype "passive"))
      (node (ref "C23") (pin "2") (pinfunction "2_2") (pintype "passive"))
      (node (ref "C3") (pin "2") (pinfunction "2_2") (pintype "passive"))
      (node (ref "C30") (pin "2") (pinfunction "2_2") (pintype "passive"))
      (node (ref "C4") (pin "1") (pinfunction "1_1") (pintype "passive"))
      (node (ref "C40") (pin "1") (pinfunction "1_1") (pintype "passive"))
      (node (ref "C45") (pin "2") (pinfunction "2_2") (pintype "passive"))
      (node (ref "C46") (pin "1") (pinfunction "1_1") (pintype "passive"))
      (node (ref "C47") (pin "2") (pinfunction "2_2") (pintype "passive"))
      (node (ref "C48") (pin "1") (pinfunction "1_1") (pintype "passive"))
      (node (ref "C5") (pin "2") (pinfunction "2_2") (pintype "passive"))
      (node (ref "C7") (pin "2") (pinfunction "2_2") (pintype "passive"))
      (node (ref "C9") (pin "1") (pinfunction "1_1") (pintype "passive"))
      (node (ref "LCD1") (pin "1") (pinfunction "NC_1") (pintype "passive"))
      (node (ref "LCD1") (pin "11") (pinfunction "R/~{W}_11") (pintype "passive"))
      (node (ref "LCD1") (pin "12") (pinfunction "E/~{RD}_12") (pintype "passive"))
      (node (ref "LCD1") (pin "16") (pinfunction "D3_16") (pintype "passive"))
      (node (ref "LCD1") (pin "17") (pinfunction "D4_17") (pintype "passive"))
      (node (ref "LCD1") (pin "18") (pinfunction "D5_18") (pintype "passive"))
      (node (ref "LCD1") (pin "19") (pinfunction "D6_19") (pintype "passive"))
      (node (ref "LCD1") (pin "2") (pinfunction "VLSS_2") (pintype "passive"))
      (node (ref "LCD1") (pin "20") (pinfunction "D7_20") (pintype "passive"))
      (node (ref "LCD1") (pin "24") (pinfunction "NC_24") (pintype "passive"))
      (node (ref "LCD1") (pin "3") (pinfunction "VSS_3") (pintype "passive"))
      (node (ref "LCD1") (pin "6") (pinfunction "BS1_6") (pintype "passive"))
      (node (ref "LCD1") (pin "7") (pinfunction "BS2_7") (pintype "passive"))
      (node (ref "LED17") (pin "2") (pinfunction "2_2") (pintype "passive"))
      (node (ref "P16") (pin "1") (pinfunction "1_1") (pintype "passive"))
      (node (ref "P9") (pin "1") (pinfunction "1_1") (pintype "passive"))
      (node (ref "R10") (pin "2") (pinfunction "2_2") (pintype "passive"))
      (node (ref "R11") (pin "2") (pinfunction "2_2") (pintype "passive"))
      (node (ref "R116") (pin "1") (pinfunction "1_1") (pintype "passive"))
      (node (ref "R117") (pin "1") (pinfunction "1_1") (pintype "passive"))
      (node (ref "R14") (pin "2") (pinfunction "2_2") (pintype "passive"))
      (node (ref "R3") (pin "1") (pinfunction "1_1") (pintype "passive"))
      (node (ref "R5") (pin "2") (pinfunction "2_2") (pintype "passive"))
      (node (ref "SW1") (pin "1") (pinfunction "1_1") (pintype "passive"))
      (node (ref "U10") (pin "2") (pinfunction "GND1_2") (pintype "passive"))
      (node (ref "U10") (pin "3") (pinfunction "GND1_3") (pintype "passive"))
      (node (ref "U10") (pin "8") (pinfunction "GND1_8") (pintype "passive"))
      (node (ref "U11") (pin "7") (pinfunction "7_7") (pintype "passive"))
      (node (ref "U12") (pin "4") (pinfunction "GND_4") (pintype "passive"))
      (node (ref "U12") (pin "9") (pinfunction "EP_9") (pintype "passive"))
      (node (ref "U2") (pin "2") (pinfunction "GND_2") (pintype "passive"))
      (node (ref "U3") (pin "2") (pinfunction "GND1_2") (pintype "passive"))
      (node (ref "U3") (pin "4") (pinfunction "~{RE}_4") (pintype "passive"))
      (node (ref "U3") (pin "8") (pinfunction "GND1_8") (pintype "passive"))
      (node (ref "U34") (pin "4") (pinfunction "SQ2_4") (pintype "passive"))
      (node (ref "U4") (pin "2") (pinfunction "-Vin_2") (pintype "passive"))
      (node (ref "U5") (pin "2") (pinfunction "-Vin_2") (pintype "passive"))
      (node (ref "U6") (pin "3") (pinfunction "GND_3") (pintype "power_in"))
      (node (ref "U8") (pin "3") (pinfunction "GND_3") (pintype "power_in"))
      (node (ref "U9") (pin "2") (pinfunction "GND_2") (pintype "power_in"))
      (node (ref "VD12") (pin "1") (pinfunction "C_1") (pintype "passive"))
      (node (ref "VD2") (pin "2") (pinfunction "2_2") (pintype "passive"))
      (node (ref "X19") (pin "5") (pinfunction "GND_5") (pintype "power_in"))
      (node (ref "X19") (pin "G1") (pinfunction "CASE_G1") (pintype "power_in"))
      (node (ref "X5") (pin "3") (pinfunction "3_3") (pintype "passive"))
      (node (ref "X5") (pin "5") (pinfunction "5_5") (pintype "passive"))
    )
    (net (code "40") (name "IGND") (class "Default")
      (node (ref "C114") (pin "1") (pinfunction "1_1") (pintype "passive"))
      (node (ref "C35") (pin "1") (pinfunction "1_1") (pintype "passive"))
      (node (ref "C41") (pin "1") (pinfunction "1_1") (pintype "passive"))
      (node (ref "C42") (pin "1") (pinfunction "1_1") (pintype "passive"))
      (node (ref "E3") (pin "1") (pinfunction "1_1") (pintype "passive"))
      (node (ref "E4") (pin "1") (pinfunction "1_1") (pintype "passive"))
      (node (ref "R117") (pin "2") (pinfunction "2_2") (pintype "passive"))
      (node (ref "U10") (pin "16") (pinfunction "GND2_16") (pintype "passive"))
      (node (ref "U10") (pin "9") (pinfunction "GND2_9") (pintype "passive"))
      (node (ref "U5") (pin "5") (pinfunction "-Vout_5") (pintype "passive"))
      (node (ref "X3") (pin "3") (pinfunction "3_3") (pintype "passive"))
      (node (ref "X4") (pin "3") (pinfunction "3_3") (pintype "passive"))
    )
    (net (code "41") (name "IGND2") (class "Default")
      (node (ref "C113") (pin "1") (pinfunction "1_1") (pintype "passive"))
      (node (ref "C8") (pin "1") (pinfunction "1_1") (pintype "passive"))
      (node (ref "R116") (pin "2") (pinfunction "2_2") (pintype "passive"))
      (node (ref "U3") (pin "15") (pinfunction "GND2_15") (pintype "passive"))
      (node (ref "U3") (pin "9") (pinfunction "GND2_9") (pintype "passive"))
      (node (ref "U4") (pin "5") (pinfunction "-Vout_5") (pintype "passive"))
      (node (ref "X1") (pin "3") (pinfunction "3_3") (pintype "passive"))
      (node (ref "X2") (pin "3") (pinfunction "3_3") (pintype "passive"))
    )
    (net (code "42") (name "IV5V") (class "Default")
      (node (ref "C35") (pin "2") (pinfunction "2_2") (pintype "passive"))
      (node (ref "C41") (pin "2") (pinfunction "2_2") (pintype "passive"))
      (node (ref "C42") (pin "2") (pinfunction "2_2") (pintype "passive"))
      (node (ref "U10") (pin "13") (pinfunction "VDD2_13") (pintype "passive"))
      (node (ref "U5") (pin "7") (pinfunction "+Vout_7") (pintype "passive"))
    )
    (net (code "43") (name "IV5V2") (class "Default")
      (node (ref "C8") (pin "2") (pinfunction "2_2") (pintype "passive"))
      (node (ref "U3") (pin "16") (pinfunction "VDD2_16") (pintype "passive"))
      (node (ref "U4") (pin "7") (pinfunction "+Vout_7") (pintype "passive"))
    )
    (net (code "44") (name "Net-(J1-Pad2)") (class "Default")
      (node (ref "J1") (pin "2") (pinfunction "2_2") (pintype "passive"))
      (node (ref "R8") (pin "1") (pinfunction "1_1") (pintype "passive"))
    )
    (net (code "45") (name "Net-(J2-Pad1)") (class "Default")
      (node (ref "J2") (pin "1") (pinfunction "1_1") (pintype "passive"))
      (node (ref "R49") (pin "2") (pinfunction "2_2") (pintype "passive"))
    )
    (net (code "46") (name "Net-(LCD1-D2)") (class "Default")
      (node (ref "LCD1") (pin "15") (pinfunction "D2_15") (pintype "passive"))
      (node (ref "R2") (pin "2") (pinfunction "2_2") (pintype "passive"))
    )
    (net (code "47") (name "Net-(LCD1-IREF)") (class "Default")
      (node (ref "LCD1") (pin "21") (pinfunction "IREF_21") (pintype "passive"))
      (node (ref "P2") (pin "1") (pinfunction "1_1") (pintype "passive"))
      (node (ref "R3") (pin "2") (pinfunction "2_2") (pintype "passive"))
    )
    (net (code "48") (name "Net-(LCD1-VH)") (class "Default")
      (node (ref "C5") (pin "1") (pinfunction "1_1") (pintype "passive"))
      (node (ref "LCD1") (pin "22") (pinfunction "VH_22") (pintype "passive"))
      (node (ref "P3") (pin "1") (pinfunction "1_1") (pintype "passive"))
    )
    (net (code "49") (name "Net-(LED17-Pad1)") (class "Default")
      (node (ref "LED17") (pin "1") (pinfunction "1_1") (pintype "passive"))
      (node (ref "R50") (pin "1") (pinfunction "1_1") (pintype "passive"))
    )
    (net (code "50") (name "Net-(P14-Pad1)") (class "Default")
      (node (ref "P14") (pin "1") (pinfunction "1_1") (pintype "passive"))
      (node (ref "R16") (pin "2") (pinfunction "2_2") (pintype "passive"))
      (node (ref "SW1") (pin "3") (pinfunction "3_3") (pintype "passive"))
    )
    (net (code "51") (name "Net-(P15-Pad1)") (class "Default")
      (node (ref "P15") (pin "1") (pinfunction "1_1") (pintype "passive"))
      (node (ref "R15") (pin "2") (pinfunction "2_2") (pintype "passive"))
      (node (ref "SW1") (pin "2") (pinfunction "2_2") (pintype "passive"))
    )
    (net (code "52") (name "Net-(U2-FB)") (class "Default")
      (node (ref "C6") (pin "2") (pinfunction "2_2") (pintype "passive"))
      (node (ref "R4") (pin "1") (pinfunction "1_1") (pintype "passive"))
      (node (ref "R5") (pin "1") (pinfunction "1_1") (pintype "passive"))
      (node (ref "U2") (pin "3") (pinfunction "FB_3") (pintype "passive"))
    )
    (net (code "53") (name "Net-(U2-SW)") (class "Default")
      (node (ref "L1") (pin "2") (pinfunction "2_2") (pintype "passive"))
      (node (ref "U2") (pin "1") (pinfunction "SW_1") (pintype "passive"))
      (node (ref "VD1") (pin "2") (pinfunction "2_2") (pintype "passive"))
    )
    (net (code "54") (name "Net-(U6-Y)") (class "Default")
      (node (ref "R15") (pin "1") (pinfunction "1_1") (pintype "passive"))
      (node (ref "U6") (pin "4") (pinfunction "Y_4") (pintype "open_collector"))
    )
    (net (code "55") (name "Net-(U8-Y)") (class "Default")
      (node (ref "R16") (pin "1") (pinfunction "1_1") (pintype "passive"))
      (node (ref "U8") (pin "4") (pinfunction "Y_4") (pintype "open_collector"))
    )
    (net (code "56") (name "Net-(U26-IN+)") (class "Default")
      (node (ref "C98") (pin "1") (pinfunction "1_1") (pintype "passive"))
      (node (ref "R106") (pin "1") (pinfunction "1_1") (pintype "passive"))
      (node (ref "R107") (pin "2") (pinfunction "2_2") (pintype "passive"))
      (node (ref "U26") (pin "3") (pinfunction "IN+_3") (pintype "passive"))
    )
    (net (code "57") (name "Net-(U26-IN-)") (class "Default")
      (node (ref "R108") (pin "2") (pinfunction "2_2") (pintype "passive"))
      (node (ref "U26") (pin "1") (pinfunction "OUT_1") (pintype "passive"))
      (node (ref "U26") (pin "4") (pinfunction "IN-_4") (pintype "passive"))
    )
    (net (code "58") (name "Net-(U34-BQ1)") (class "Default")
      (node (ref "U34") (pin "3") (pinfunction "DQ2_3") (pintype "passive"))
      (node (ref "U34") (pin "5") (pinfunction "BQ1_5") (pintype "passive"))
    )
    (net (code "59") (name "Net-(X19-VBUS)") (class "Default")
      (node (ref "C45") (pin "1") (pinfunction "1_1") (pintype "passive"))
      (node (ref "L4") (pin "1") (pinfunction "1_1") (pintype "passive"))
      (node (ref "U11") (pin "6") (pinfunction "6_6") (pintype "passive"))
      (node (ref "X19") (pin "1") (pinfunction "VBUS_1") (pintype "power_in"))
    )
    (net (code "60") (name "PWR24F") (class "Default")
      (node (ref "C23") (pin "1") (pinfunction "1_1") (pintype "passive"))
      (node (ref "F1") (pin "2") (pinfunction "2_2") (pintype "passive"))
      (node (ref "U9") (pin "1") (pinfunction "IN_1") (pintype "power_in"))
      (node (ref "VD2") (pin "1") (pinfunction "1_1") (pintype "passive"))
    )
    (net (code "61") (name "SYS_PWR") (class "Default")
      (node (ref "F1") (pin "1") (pinfunction "1_1") (pintype "passive"))
    )
    (net (code "62") (name "VREF_1.65V") (class "Default")
      (node (ref "C99") (pin "1") (pinfunction "1_1") (pintype "passive"))
      (node (ref "R108") (pin "1") (pinfunction "1_1") (pintype "passive"))
    )
    (net (code "63") (name "unconnected-(H2-Pad0)") (class "Default")
      (node (ref "H2") (pin "0") (pinfunction "0_0") (pintype "passive"))
    )
    (net (code "64") (name "unconnected-(H3-Pad0)") (class "Default")
      (node (ref "H3") (pin "0") (pinfunction "0_0") (pintype "passive"))
    )
    (net (code "65") (name "unconnected-(H4-Pad0)") (class "Default")
      (node (ref "H4") (pin "0") (pinfunction "0_0") (pintype "passive"))
    )
    (net (code "66") (name "unconnected-(LCD1-NC-Pad4)") (class "Default")
      (node (ref "LCD1") (pin "4") (pinfunction "NC_4") (pintype "passive"))
    )
    (net (code "67") (name "unconnected-(U3-NC-Pad10)") (class "Default")
      (node (ref "U3") (pin "10") (pinfunction "NC_10") (pintype "passive"))
    )
    (net (code "68") (name "unconnected-(U3-NC-Pad11)") (class "Default")
      (node (ref "U3") (pin "11") (pinfunction "NC_11") (pintype "passive"))
    )
    (net (code "69") (name "unconnected-(U3-NC-Pad14)") (class "Default")
      (node (ref "U3") (pin "14") (pinfunction "NC_14") (pintype "passive"))
    )
    (net (code "70") (name "unconnected-(U3-PV-Pad7)") (class "Default")
      (node (ref "U3") (pin "7") (pinfunction "PV_7") (pintype "passive"))
    )
    (net (code "71") (name "unconnected-(U10-NC-Pad1)") (class "Default")
      (node (ref "U10") (pin "1") (pinfunction "NC_1") (pintype "passive"))
    )
    (net (code "72") (name "unconnected-(U10-NC-Pad14)") (class "Default")
      (node (ref "U10") (pin "14") (pinfunction "NC_14") (pintype "passive"))
    )
    (net (code "73") (name "unconnected-(U10-NC-Pad15)") (class "Default")
      (node (ref "U10") (pin "15") (pinfunction "NC_15") (pintype "passive"))
    )
    (net (code "74") (name "unconnected-(U10-VREF-Pad10)") (class "Default")
      (node (ref "U10") (pin "10") (pinfunction "VREF_10") (pintype "passive"))
    )
    (net (code "75") (name "unconnected-(X5-Pad7)") (class "Default")
      (node (ref "X5") (pin "7") (pinfunction "7_7") (pintype "passive"))
    )
    (net (code "76") (name "unconnected-(X5-Pad8)") (class "Default")
      (node (ref "X5") (pin "8") (pinfunction "8_8") (pintype "passive"))
    )
    (net (code "77") (name "unconnected-(X5-Pad9)") (class "Default")
      (node (ref "X5") (pin "9") (pinfunction "9_9") (pintype "passive"))
    )
  )
)
